# BMS_IC.net
KiCad netlist of a schematic drawn in Altium Designer
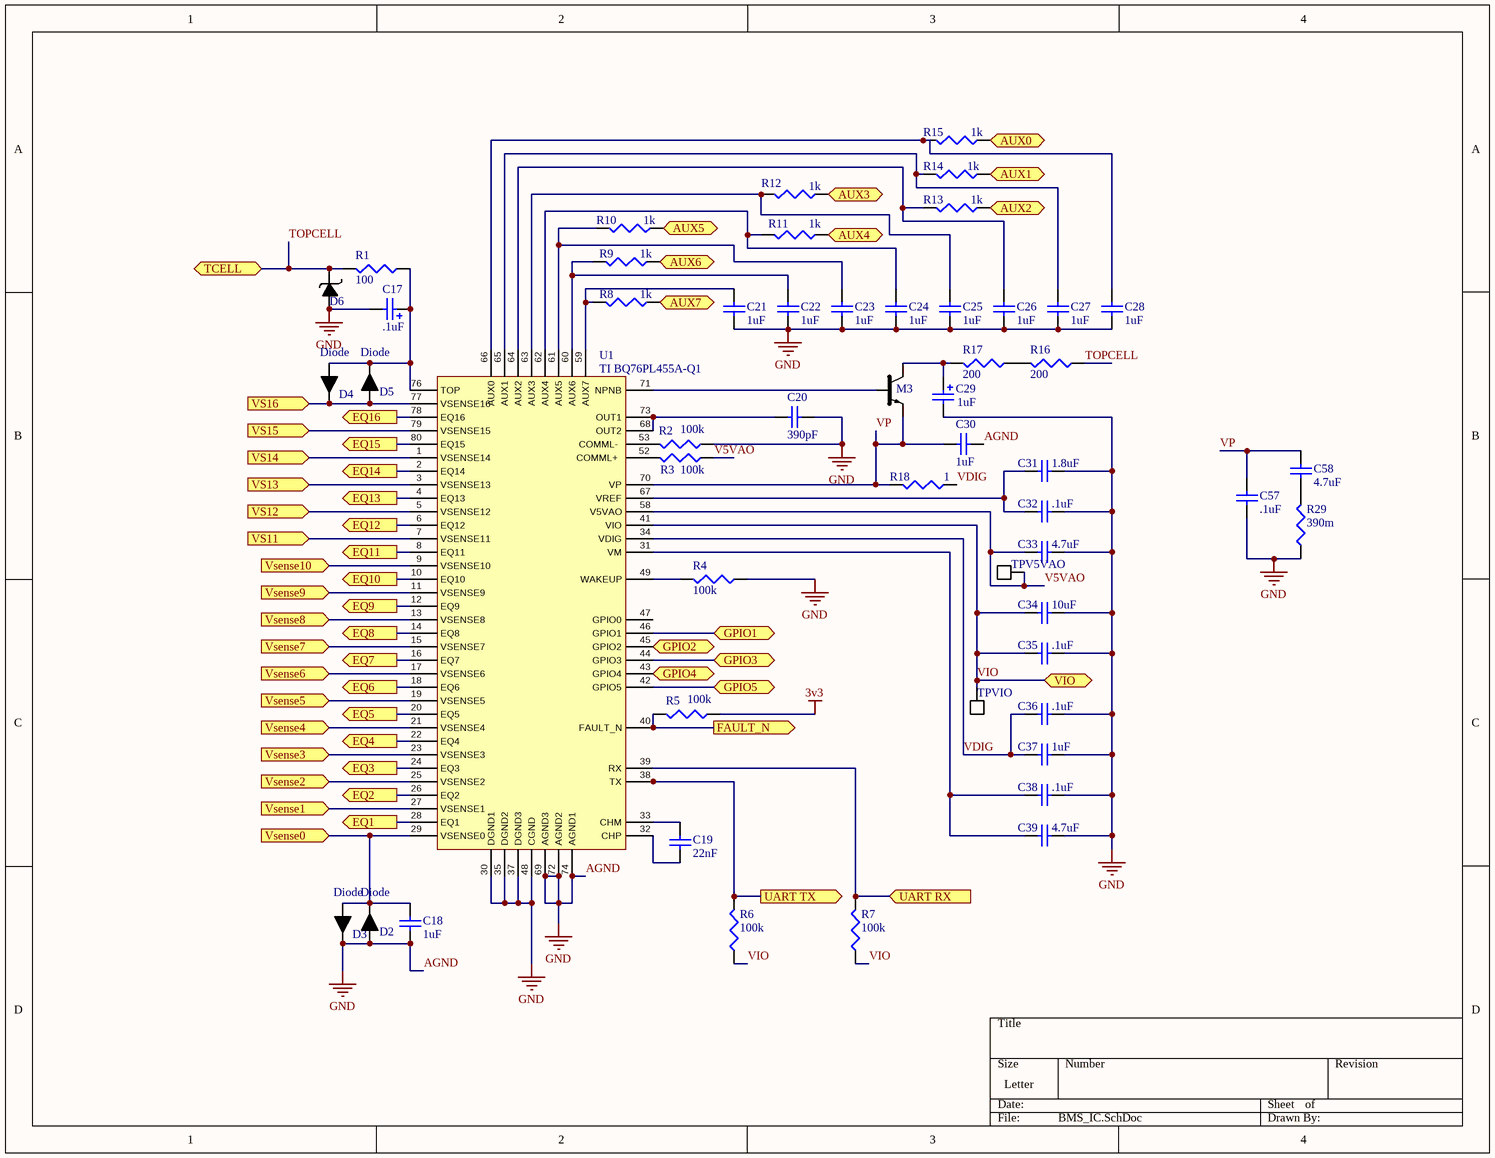
[diagram p0: BMS_IC.SchDoc]

(export (version "E")
  (design (tool "Eeschema 10.0.6"))
  (components
    (comp (ref "C17")
      (value ".1uF")
      (footprint "SMD1206 Polarized")
      (description "Polarized Capacitor (Surface Mount)")
      (fields (field (name "Comment") "Cap"))
      (libsource (lib "Components") (part "Capacitor Polarized"))
    )
    (comp (ref "C18")
      (value "1uF")
      (footprint "SMD0603")
      (description "Ceramic Chip Capacitor")
      (fields (field (name "Comment") "Cap"))
      (libsource (lib "Components") (part "Capacitor Ceramic"))
    )
    (comp (ref "C19")
      (value "22nF")
      (footprint "SMD0603")
      (description "Ceramic Chip Capacitor")
      (fields (field (name "Comment") "Cap"))
      (libsource (lib "Components") (part "Capacitor Ceramic"))
    )
    (comp (ref "C20")
      (value "390pF")
      (footprint "SMD0805")
      (description "Ceramic Chip Capacitor")
      (fields (field (name "Comment") "Cap"))
      (libsource (lib "Components") (part "Capacitor Ceramic"))
    )
    (comp (ref "C21")
      (value "1uF")
      (footprint "SMD0603")
      (description "Ceramic Chip Capacitor")
      (fields (field (name "Comment") "Cap"))
      (libsource (lib "Components") (part "Capacitor Ceramic"))
    )
    (comp (ref "C22")
      (value "1uF")
      (footprint "SMD0603")
      (description "Ceramic Chip Capacitor")
      (fields (field (name "Comment") "Cap"))
      (libsource (lib "Components") (part "Capacitor Ceramic"))
    )
    (comp (ref "C23")
      (value "1uF")
      (footprint "SMD0603")
      (description "Ceramic Chip Capacitor")
      (fields (field (name "Comment") "Cap"))
      (libsource (lib "Components") (part "Capacitor Ceramic"))
    )
    (comp (ref "C24")
      (value "1uF")
      (footprint "SMD0603")
      (description "Ceramic Chip Capacitor")
      (fields (field (name "Comment") "Cap"))
      (libsource (lib "Components") (part "Capacitor Ceramic"))
    )
    (comp (ref "C25")
      (value "1uF")
      (footprint "SMD0603")
      (description "Ceramic Chip Capacitor")
      (fields (field (name "Comment") "Cap"))
      (libsource (lib "Components") (part "Capacitor Ceramic"))
    )
    (comp (ref "C26")
      (value "1uF")
      (footprint "SMD0603")
      (description "Ceramic Chip Capacitor")
      (fields (field (name "Comment") "Cap"))
      (libsource (lib "Components") (part "Capacitor Ceramic"))
    )
    (comp (ref "C27")
      (value "1uF")
      (footprint "SMD0603")
      (description "Ceramic Chip Capacitor")
      (fields (field (name "Comment") "Cap"))
      (libsource (lib "Components") (part "Capacitor Ceramic"))
    )
    (comp (ref "C28")
      (value "1uF")
      (footprint "SMD0603")
      (description "Ceramic Chip Capacitor")
      (fields (field (name "Comment") "Cap"))
      (libsource (lib "Components") (part "Capacitor Ceramic"))
    )
    (comp (ref "C29")
      (value "1uF")
      (footprint "SMD1206 Polarized")
      (description "Polarized Capacitor (Surface Mount)")
      (fields (field (name "Comment") "Cap"))
      (libsource (lib "Components") (part "Capacitor Polarized"))
    )
    (comp (ref "C30")
      (value "1uF")
      (footprint "SMD0603")
      (description "Ceramic Chip Capacitor")
      (fields (field (name "Comment") "Cap"))
      (libsource (lib "Components") (part "Capacitor Ceramic"))
    )
    (comp (ref "C31")
      (value "1.8uF")
      (footprint "SMD0603")
      (description "Ceramic Chip Capacitor")
      (fields (field (name "Comment") "Cap"))
      (libsource (lib "Components") (part "Capacitor Ceramic"))
    )
    (comp (ref "C32")
      (value ".1uF")
      (footprint "SMD0603")
      (description "Ceramic Chip Capacitor")
      (fields (field (name "Comment") "Cap"))
      (libsource (lib "Components") (part "Capacitor Ceramic"))
    )
    (comp (ref "C33")
      (value "4.7uF")
      (footprint "SMD0603")
      (description "Ceramic Chip Capacitor")
      (fields (field (name "Comment") "Cap"))
      (libsource (lib "Components") (part "Capacitor Ceramic"))
    )
    (comp (ref "C34")
      (value "10uF")
      (footprint "SMD0603")
      (description "Ceramic Chip Capacitor")
      (fields (field (name "Comment") "Cap"))
      (libsource (lib "Components") (part "Capacitor Ceramic"))
    )
    (comp (ref "C35")
      (value ".1uF")
      (footprint "SMD0603")
      (description "Ceramic Chip Capacitor")
      (fields (field (name "Comment") "Cap"))
      (libsource (lib "Components") (part "Capacitor Ceramic"))
    )
    (comp (ref "C36")
      (value ".1uF")
      (footprint "SMD0603")
      (description "Ceramic Chip Capacitor")
      (fields (field (name "Comment") "Cap"))
      (libsource (lib "Components") (part "Capacitor Ceramic"))
    )
    (comp (ref "C37")
      (value "1uF")
      (footprint "SMD0603")
      (description "Ceramic Chip Capacitor")
      (fields (field (name "Comment") "Cap"))
      (libsource (lib "Components") (part "Capacitor Ceramic"))
    )
    (comp (ref "C38")
      (value ".1uF")
      (footprint "SMD0603")
      (description "Ceramic Chip Capacitor")
      (fields (field (name "Comment") "Cap"))
      (libsource (lib "Components") (part "Capacitor Ceramic"))
    )
    (comp (ref "C39")
      (value "4.7uF")
      (footprint "SMD0603")
      (description "Ceramic Chip Capacitor")
      (fields (field (name "Comment") "Cap"))
      (libsource (lib "Components") (part "Capacitor Ceramic"))
    )
    (comp (ref "C57")
      (value ".1uF")
      (footprint "SMD0603")
      (description "Ceramic Chip Capacitor")
      (fields (field (name "Comment") "Cap"))
      (libsource (lib "Components") (part "Capacitor Ceramic"))
    )
    (comp (ref "C58")
      (value "4.7uF")
      (footprint "SMD0603")
      (description "Ceramic Chip Capacitor")
      (fields (field (name "Comment") "Cap"))
      (libsource (lib "Components") (part "Capacitor Ceramic"))
    )
    (comp (ref "D2") (value "Diode") (footprint "DPAK23") (libsource (lib "Components") (part "Diode")))
    (comp (ref "D3") (value "Diode") (footprint "DPAK23") (libsource (lib "Components") (part "Diode")))
    (comp (ref "D4") (value "Diode") (footprint "DPAK23") (libsource (lib "Components") (part "Diode")))
    (comp (ref "D5") (value "Diode") (footprint "DPAK23") (libsource (lib "Components") (part "Diode")))
    (comp (ref "D6")
      (value "Zener Diode")
      (footprint "DPAK M:TVS Diode")
      (libsource (lib "Components") (part "Zener Diode"))
    )
    (comp (ref "M3") (value "BJT") (footprint "SOT23") (libsource (lib "Schlib1") (part "BJT")))
    (comp (ref "R1")
      (value "100")
      (footprint "SMD0603")
      (description "Resistor")
      (fields (field (name "Comment") "Res"))
      (libsource (lib "Components") (part "Resistor"))
    )
    (comp (ref "R2")
      (value "100k")
      (footprint "SMD0603")
      (description "Resistor")
      (fields (field (name "Comment") "Res"))
      (libsource (lib "Components") (part "Resistor"))
    )
    (comp (ref "R3")
      (value "100k")
      (footprint "SMD0603")
      (description "Resistor")
      (fields (field (name "Comment") "Res"))
      (libsource (lib "Components") (part "Resistor"))
    )
    (comp (ref "R4")
      (value "100k")
      (footprint "SMD0603")
      (description "Resistor")
      (fields (field (name "Comment") "Res"))
      (libsource (lib "Components") (part "Resistor"))
    )
    (comp (ref "R5")
      (value "100k")
      (footprint "SMD0603")
      (description "Resistor")
      (fields (field (name "Comment") "Res"))
      (libsource (lib "Components") (part "Resistor"))
    )
    (comp (ref "R6")
      (value "100k")
      (footprint "SMD0603")
      (description "Resistor")
      (fields (field (name "Comment") "Res"))
      (libsource (lib "Components") (part "Resistor"))
    )
    (comp (ref "R7")
      (value "100k")
      (footprint "SMD0603")
      (description "Resistor")
      (fields (field (name "Comment") "Res"))
      (libsource (lib "Components") (part "Resistor"))
    )
    (comp (ref "R8")
      (value "1k")
      (footprint "SMD0603")
      (description "Resistor")
      (fields (field (name "Comment") "Res"))
      (libsource (lib "Components") (part "Resistor"))
    )
    (comp (ref "R9")
      (value "1k")
      (footprint "SMD0603")
      (description "Resistor")
      (fields (field (name "Comment") "Res"))
      (libsource (lib "Components") (part "Resistor"))
    )
    (comp (ref "R10")
      (value "1k")
      (footprint "SMD0603")
      (description "Resistor")
      (fields (field (name "Comment") "Res"))
      (libsource (lib "Components") (part "Resistor"))
    )
    (comp (ref "R11")
      (value "1k")
      (footprint "SMD0603")
      (description "Resistor")
      (fields (field (name "Comment") "Res"))
      (libsource (lib "Components") (part "Resistor"))
    )
    (comp (ref "R12")
      (value "1k")
      (footprint "SMD0603")
      (description "Resistor")
      (fields (field (name "Comment") "Res"))
      (libsource (lib "Components") (part "Resistor"))
    )
    (comp (ref "R13")
      (value "1k")
      (footprint "SMD0603")
      (description "Resistor")
      (fields (field (name "Comment") "Res"))
      (libsource (lib "Components") (part "Resistor"))
    )
    (comp (ref "R14")
      (value "1k")
      (footprint "SMD0603")
      (description "Resistor")
      (fields (field (name "Comment") "Res"))
      (libsource (lib "Components") (part "Resistor"))
    )
    (comp (ref "R15")
      (value "1k")
      (footprint "SMD0603")
      (description "Resistor")
      (fields (field (name "Comment") "Res"))
      (libsource (lib "Components") (part "Resistor"))
    )
    (comp (ref "R16")
      (value "200")
      (footprint "SMD0603")
      (description "Resistor")
      (fields (field (name "Comment") "Res"))
      (libsource (lib "Components") (part "Resistor"))
    )
    (comp (ref "R17")
      (value "200")
      (footprint "SMD0603")
      (description "Resistor")
      (fields (field (name "Comment") "Res"))
      (libsource (lib "Components") (part "Resistor"))
    )
    (comp (ref "R18")
      (value "1")
      (footprint "SMD0603")
      (description "Resistor")
      (fields (field (name "Comment") "Res"))
      (libsource (lib "Components") (part "Resistor"))
    )
    (comp (ref "R29")
      (value "390m")
      (footprint "SMD0603")
      (description "Resistor")
      (fields (field (name "Comment") "Res"))
      (libsource (lib "Components") (part "Resistor"))
    )
    (comp (ref "TPV5VAO")
      (value "Test Point")
      (footprint "Test Point")
      (libsource (lib "Components") (part "Test Point"))
    )
    (comp (ref "TPVIO")
      (value "Test Point")
      (footprint "Test Point")
      (libsource (lib "Components") (part "Test Point"))
    )
    (comp (ref "U1")
      (value "TI BQ76PL455A-Q1")
      (footprint "TQFP-80")
      (libsource (lib "SEM_BMS") (part "TI BQ76PL455A-Q1"))
    )
  )
  (nets
    (net (code "1") (name "/AUX0") (class "Default")
      (node (ref "R15") (pin "1") (pinfunction "1_1") (pintype "passive"))
    )
    (net (code "2") (name "/AUX1") (class "Default")
      (node (ref "R14") (pin "1") (pinfunction "1_1") (pintype "passive"))
    )
    (net (code "3") (name "/AUX2") (class "Default")
      (node (ref "R13") (pin "1") (pinfunction "1_1") (pintype "passive"))
    )
    (net (code "4") (name "/AUX3") (class "Default")
      (node (ref "R12") (pin "1") (pinfunction "1_1") (pintype "passive"))
    )
    (net (code "5") (name "/AUX4") (class "Default")
      (node (ref "R11") (pin "1") (pinfunction "1_1") (pintype "passive"))
    )
    (net (code "6") (name "/AUX5") (class "Default")
      (node (ref "R10") (pin "1") (pinfunction "1_1") (pintype "passive"))
    )
    (net (code "7") (name "/AUX6") (class "Default")
      (node (ref "R9") (pin "1") (pinfunction "1_1") (pintype "passive"))
    )
    (net (code "8") (name "/AUX7") (class "Default")
      (node (ref "R8") (pin "1") (pinfunction "1_1") (pintype "passive"))
    )
    (net (code "9") (name "/EQ1") (class "Default")
      (node (ref "U1") (pin "28") (pinfunction "EQ1_28") (pintype "passive"))
    )
    (net (code "10") (name "/EQ2") (class "Default")
      (node (ref "U1") (pin "26") (pinfunction "EQ2_26") (pintype "passive"))
    )
    (net (code "11") (name "/EQ3") (class "Default")
      (node (ref "U1") (pin "24") (pinfunction "EQ3_24") (pintype "passive"))
    )
    (net (code "12") (name "/EQ4") (class "Default")
      (node (ref "U1") (pin "22") (pinfunction "EQ4_22") (pintype "passive"))
    )
    (net (code "13") (name "/EQ5") (class "Default")
      (node (ref "U1") (pin "20") (pinfunction "EQ5_20") (pintype "passive"))
    )
    (net (code "14") (name "/EQ6") (class "Default")
      (node (ref "U1") (pin "18") (pinfunction "EQ6_18") (pintype "passive"))
    )
    (net (code "15") (name "/EQ7") (class "Default")
      (node (ref "U1") (pin "16") (pinfunction "EQ7_16") (pintype "passive"))
    )
    (net (code "16") (name "/EQ8") (class "Default")
      (node (ref "U1") (pin "14") (pinfunction "EQ8_14") (pintype "passive"))
    )
    (net (code "17") (name "/EQ9") (class "Default")
      (node (ref "U1") (pin "12") (pinfunction "EQ9_12") (pintype "passive"))
    )
    (net (code "18") (name "/EQ10") (class "Default")
      (node (ref "U1") (pin "10") (pinfunction "EQ10_10") (pintype "passive"))
    )
    (net (code "19") (name "/EQ11") (class "Default")
      (node (ref "U1") (pin "8") (pinfunction "EQ11_8") (pintype "passive"))
    )
    (net (code "20") (name "/EQ12") (class "Default")
      (node (ref "U1") (pin "6") (pinfunction "EQ12_6") (pintype "passive"))
    )
    (net (code "21") (name "/EQ13") (class "Default")
      (node (ref "U1") (pin "4") (pinfunction "EQ13_4") (pintype "passive"))
    )
    (net (code "22") (name "/EQ14") (class "Default")
      (node (ref "U1") (pin "2") (pinfunction "EQ14_2") (pintype "passive"))
    )
    (net (code "23") (name "/EQ15") (class "Default")
      (node (ref "U1") (pin "80") (pinfunction "EQ15_80") (pintype "passive"))
    )
    (net (code "24") (name "/EQ16") (class "Default")
      (node (ref "U1") (pin "78") (pinfunction "EQ16_78") (pintype "passive"))
    )
    (net (code "25") (name "/FAULT_N") (class "Default")
      (node (ref "R5") (pin "2") (pinfunction "2_2") (pintype "passive"))
      (node (ref "U1") (pin "40") (pinfunction "FAULT_N_40") (pintype "passive"))
    )
    (net (code "26") (name "/GPIO1") (class "Default")
      (node (ref "U1") (pin "46") (pinfunction "GPIO1_46") (pintype "passive"))
    )
    (net (code "27") (name "/GPIO2") (class "Default")
      (node (ref "U1") (pin "45") (pinfunction "GPIO2_45") (pintype "passive"))
    )
    (net (code "28") (name "/GPIO3") (class "Default")
      (node (ref "U1") (pin "44") (pinfunction "GPIO3_44") (pintype "passive"))
    )
    (net (code "29") (name "/GPIO4") (class "Default")
      (node (ref "U1") (pin "43") (pinfunction "GPIO4_43") (pintype "passive"))
    )
    (net (code "30") (name "/GPIO5") (class "Default")
      (node (ref "U1") (pin "42") (pinfunction "GPIO5_42") (pintype "passive"))
    )
    (net (code "31") (name "/TOPCELL") (class "Default")
      (node (ref "D6") (pin "2") (pinfunction "2_2") (pintype "passive"))
      (node (ref "R1") (pin "2") (pinfunction "2_2") (pintype "passive"))
      (node (ref "R16") (pin "1") (pinfunction "1_1") (pintype "passive"))
    )
    (net (code "32") (name "/UART RX") (class "Default")
      (node (ref "R7") (pin "2") (pinfunction "2_2") (pintype "passive"))
      (node (ref "U1") (pin "39") (pinfunction "RX_39") (pintype "passive"))
    )
    (net (code "33") (name "/UART TX") (class "Default")
      (node (ref "R6") (pin "2") (pinfunction "2_2") (pintype "passive"))
      (node (ref "U1") (pin "38") (pinfunction "TX_38") (pintype "passive"))
    )
    (net (code "34") (name "/V5VAO") (class "Default")
      (node (ref "C33") (pin "2") (pinfunction "2_2") (pintype "passive"))
      (node (ref "R3") (pin "1") (pinfunction "1_1") (pintype "passive"))
      (node (ref "TPV5VAO") (pin "1") (pinfunction "1_1") (pintype "passive"))
      (node (ref "U1") (pin "58") (pinfunction "V5VAO_58") (pintype "passive"))
    )
    (net (code "35") (name "/VDIG") (class "Default")
      (node (ref "C36") (pin "2") (pinfunction "2_2") (pintype "passive"))
      (node (ref "C37") (pin "2") (pinfunction "2_2") (pintype "passive"))
      (node (ref "R18") (pin "1") (pinfunction "1_1") (pintype "passive"))
      (node (ref "U1") (pin "34") (pinfunction "VDIG_34") (pintype "passive"))
    )
    (net (code "36") (name "/VIO") (class "Default")
      (node (ref "C34") (pin "2") (pinfunction "2_2") (pintype "passive"))
      (node (ref "C35") (pin "2") (pinfunction "2_2") (pintype "passive"))
      (node (ref "R6") (pin "1") (pinfunction "1_1") (pintype "passive"))
      (node (ref "R7") (pin "1") (pinfunction "1_1") (pintype "passive"))
      (node (ref "TPVIO") (pin "1") (pinfunction "1_1") (pintype "passive"))
      (node (ref "U1") (pin "41") (pinfunction "VIO_41") (pintype "passive"))
    )
    (net (code "37") (name "/VP") (class "Default")
      (node (ref "C30") (pin "2") (pinfunction "2_2") (pintype "passive"))
      (node (ref "C57") (pin "2") (pinfunction "2_2") (pintype "passive"))
      (node (ref "C58") (pin "2") (pinfunction "2_2") (pintype "passive"))
      (node (ref "M3") (pin "3") (pintype "passive"))
      (node (ref "R18") (pin "2") (pinfunction "2_2") (pintype "passive"))
      (node (ref "U1") (pin "70") (pinfunction "VP_70") (pintype "passive"))
    )
    (net (code "38") (name "/VS11") (class "Default")
      (node (ref "U1") (pin "7") (pinfunction "VSENSE11_7") (pintype "passive"))
    )
    (net (code "39") (name "/VS12") (class "Default")
      (node (ref "U1") (pin "5") (pinfunction "VSENSE12_5") (pintype "passive"))
    )
    (net (code "40") (name "/VS13") (class "Default")
      (node (ref "U1") (pin "3") (pinfunction "VSENSE13_3") (pintype "passive"))
    )
    (net (code "41") (name "/VS14") (class "Default")
      (node (ref "U1") (pin "1") (pinfunction "VSENSE14_1") (pintype "passive"))
    )
    (net (code "42") (name "/VS15") (class "Default")
      (node (ref "U1") (pin "79") (pinfunction "VSENSE15_79") (pintype "passive"))
    )
    (net (code "43") (name "/VS16") (class "Default")
      (node (ref "D4") (pin "2") (pinfunction "Cathode_(-)_2") (pintype "passive"))
      (node (ref "D5") (pin "3") (pinfunction "Anode_(+)_3") (pintype "passive"))
      (node (ref "U1") (pin "77") (pinfunction "VSENSE16_77") (pintype "passive"))
    )
    (net (code "44") (name "/Vsense0") (class "Default")
      (node (ref "C18") (pin "2") (pinfunction "2_2") (pintype "passive"))
      (node (ref "D2") (pin "2") (pinfunction "Cathode_(-)_2") (pintype "passive"))
      (node (ref "D3") (pin "3") (pinfunction "Anode_(+)_3") (pintype "passive"))
      (node (ref "U1") (pin "29") (pinfunction "VSENSE0_29") (pintype "passive"))
    )
    (net (code "45") (name "/Vsense1") (class "Default")
      (node (ref "U1") (pin "27") (pinfunction "VSENSE1_27") (pintype "passive"))
    )
    (net (code "46") (name "/Vsense2") (class "Default")
      (node (ref "U1") (pin "25") (pinfunction "VSENSE2_25") (pintype "passive"))
    )
    (net (code "47") (name "/Vsense3") (class "Default")
      (node (ref "U1") (pin "23") (pinfunction "VSENSE3_23") (pintype "passive"))
    )
    (net (code "48") (name "/Vsense4") (class "Default")
      (node (ref "U1") (pin "21") (pinfunction "VSENSE4_21") (pintype "passive"))
    )
    (net (code "49") (name "/Vsense5") (class "Default")
      (node (ref "U1") (pin "19") (pinfunction "VSENSE5_19") (pintype "passive"))
    )
    (net (code "50") (name "/Vsense6") (class "Default")
      (node (ref "U1") (pin "17") (pinfunction "VSENSE6_17") (pintype "passive"))
    )
    (net (code "51") (name "/Vsense7") (class "Default")
      (node (ref "U1") (pin "15") (pinfunction "VSENSE7_15") (pintype "passive"))
    )
    (net (code "52") (name "/Vsense8") (class "Default")
      (node (ref "U1") (pin "13") (pinfunction "VSENSE8_13") (pintype "passive"))
    )
    (net (code "53") (name "/Vsense9") (class "Default")
      (node (ref "U1") (pin "11") (pinfunction "VSENSE9_11") (pintype "passive"))
    )
    (net (code "54") (name "/Vsense10") (class "Default")
      (node (ref "U1") (pin "9") (pinfunction "VSENSE10_9") (pintype "passive"))
    )
    (net (code "55") (name "3v3") (class "Default")
      (node (ref "R5") (pin "1") (pinfunction "1_1") (pintype "passive"))
    )
    (net (code "56") (name "GND") (class "Default")
      (node (ref "C17") (pin "2") (pinfunction "2_2") (pintype "passive"))
      (node (ref "C18") (pin "1") (pinfunction "1_1") (pintype "passive"))
      (node (ref "C20") (pin "1") (pinfunction "1_1") (pintype "passive"))
      (node (ref "C21") (pin "1") (pinfunction "1_1") (pintype "passive"))
      (node (ref "C22") (pin "1") (pinfunction "1_1") (pintype "passive"))
      (node (ref "C23") (pin "1") (pinfunction "1_1") (pintype "passive"))
      (node (ref "C24") (pin "1") (pinfunction "1_1") (pintype "passive"))
      (node (ref "C25") (pin "1") (pinfunction "1_1") (pintype "passive"))
      (node (ref "C26") (pin "1") (pinfunction "1_1") (pintype "passive"))
      (node (ref "C27") (pin "1") (pinfunction "1_1") (pintype "passive"))
      (node (ref "C28") (pin "1") (pinfunction "1_1") (pintype "passive"))
      (node (ref "C29") (pin "2") (pinfunction "2_2") (pintype "passive"))
      (node (ref "C30") (pin "1") (pinfunction "1_1") (pintype "passive"))
      (node (ref "C31") (pin "1") (pinfunction "1_1") (pintype "passive"))
      (node (ref "C32") (pin "1") (pinfunction "1_1") (pintype "passive"))
      (node (ref "C33") (pin "1") (pinfunction "1_1") (pintype "passive"))
      (node (ref "C34") (pin "1") (pinfunction "1_1") (pintype "passive"))
      (node (ref "C35") (pin "1") (pinfunction "1_1") (pintype "passive"))
      (node (ref "C36") (pin "1") (pinfunction "1_1") (pintype "passive"))
      (node (ref "C37") (pin "1") (pinfunction "1_1") (pintype "passive"))
      (node (ref "C38") (pin "1") (pinfunction "1_1") (pintype "passive"))
      (node (ref "C39") (pin "1") (pinfunction "1_1") (pintype "passive"))
      (node (ref "C57") (pin "1") (pinfunction "1_1") (pintype "passive"))
      (node (ref "D2") (pin "3") (pinfunction "Anode_(+)_3") (pintype "passive"))
      (node (ref "D3") (pin "2") (pinfunction "Cathode_(-)_2") (pintype "passive"))
      (node (ref "D6") (pin "1") (pintype "passive"))
      (node (ref "R2") (pin "1") (pinfunction "1_1") (pintype "passive"))
      (node (ref "R29") (pin "1") (pinfunction "1_1") (pintype "passive"))
      (node (ref "R4") (pin "1") (pinfunction "1_1") (pintype "passive"))
      (node (ref "U1") (pin "30") (pinfunction "DGND1_30") (pintype "passive"))
      (node (ref "U1") (pin "35") (pinfunction "DGND2_35") (pintype "passive"))
      (node (ref "U1") (pin "37") (pinfunction "DGND3_37") (pintype "passive"))
      (node (ref "U1") (pin "48") (pinfunction "CGND_48") (pintype "passive"))
      (node (ref "U1") (pin "69") (pinfunction "AGND3_69") (pintype "passive"))
      (node (ref "U1") (pin "72") (pinfunction "AGND2_72") (pintype "passive"))
      (node (ref "U1") (pin "74") (pinfunction "AGND1_74") (pintype "passive"))
    )
    (net (code "57") (name "Net-(C29-Pad1)") (class "Default")
      (node (ref "C29") (pin "1") (pinfunction "1_1") (pintype "passive"))
      (node (ref "M3") (pin "1") (pintype "passive"))
      (node (ref "R17") (pin "2") (pinfunction "2_2") (pintype "passive"))
    )
    (net (code "58") (name "Net-(C58-Pad1)") (class "Default")
      (node (ref "C58") (pin "1") (pinfunction "1_1") (pintype "passive"))
      (node (ref "R29") (pin "2") (pinfunction "2_2") (pintype "passive"))
    )
    (net (code "59") (name "Net-(D4-Anode_(+))") (class "Default")
      (node (ref "C17") (pin "1") (pinfunction "1_1") (pintype "passive"))
      (node (ref "D4") (pin "3") (pinfunction "Anode_(+)_3") (pintype "passive"))
      (node (ref "D5") (pin "2") (pinfunction "Cathode_(-)_2") (pintype "passive"))
      (node (ref "R1") (pin "1") (pinfunction "1_1") (pintype "passive"))
      (node (ref "U1") (pin "76") (pinfunction "TOP_76") (pintype "passive"))
    )
    (net (code "60") (name "Net-(R16-Pad2)") (class "Default")
      (node (ref "R16") (pin "2") (pinfunction "2_2") (pintype "passive"))
      (node (ref "R17") (pin "1") (pinfunction "1_1") (pintype "passive"))
    )
    (net (code "61") (name "Net-(U1-AUX0)") (class "Default")
      (node (ref "C28") (pin "2") (pinfunction "2_2") (pintype "passive"))
      (node (ref "R15") (pin "2") (pinfunction "2_2") (pintype "passive"))
      (node (ref "U1") (pin "66") (pinfunction "AUX0_66") (pintype "passive"))
    )
    (net (code "62") (name "Net-(U1-AUX1)") (class "Default")
      (node (ref "C27") (pin "2") (pinfunction "2_2") (pintype "passive"))
      (node (ref "R14") (pin "2") (pinfunction "2_2") (pintype "passive"))
      (node (ref "U1") (pin "65") (pinfunction "AUX1_65") (pintype "passive"))
    )
    (net (code "63") (name "Net-(U1-AUX2)") (class "Default")
      (node (ref "C26") (pin "2") (pinfunction "2_2") (pintype "passive"))
      (node (ref "R13") (pin "2") (pinfunction "2_2") (pintype "passive"))
      (node (ref "U1") (pin "64") (pinfunction "AUX2_64") (pintype "passive"))
    )
    (net (code "64") (name "Net-(U1-AUX3)") (class "Default")
      (node (ref "C25") (pin "2") (pinfunction "2_2") (pintype "passive"))
      (node (ref "R12") (pin "2") (pinfunction "2_2") (pintype "passive"))
      (node (ref "U1") (pin "63") (pinfunction "AUX3_63") (pintype "passive"))
    )
    (net (code "65") (name "Net-(U1-AUX4)") (class "Default")
      (node (ref "C24") (pin "2") (pinfunction "2_2") (pintype "passive"))
      (node (ref "R11") (pin "2") (pinfunction "2_2") (pintype "passive"))
      (node (ref "U1") (pin "62") (pinfunction "AUX4_62") (pintype "passive"))
    )
    (net (code "66") (name "Net-(U1-AUX5)") (class "Default")
      (node (ref "C23") (pin "2") (pinfunction "2_2") (pintype "passive"))
      (node (ref "R10") (pin "2") (pinfunction "2_2") (pintype "passive"))
      (node (ref "U1") (pin "61") (pinfunction "AUX5_61") (pintype "passive"))
    )
    (net (code "67") (name "Net-(U1-AUX6)") (class "Default")
      (node (ref "C22") (pin "2") (pinfunction "2_2") (pintype "passive"))
      (node (ref "R9") (pin "2") (pinfunction "2_2") (pintype "passive"))
      (node (ref "U1") (pin "60") (pinfunction "AUX6_60") (pintype "passive"))
    )
    (net (code "68") (name "Net-(U1-AUX7)") (class "Default")
      (node (ref "C21") (pin "2") (pinfunction "2_2") (pintype "passive"))
      (node (ref "R8") (pin "2") (pinfunction "2_2") (pintype "passive"))
      (node (ref "U1") (pin "59") (pinfunction "AUX7_59") (pintype "passive"))
    )
    (net (code "69") (name "Net-(U1-CHM)") (class "Default")
      (node (ref "C19") (pin "2") (pinfunction "2_2") (pintype "passive"))
      (node (ref "U1") (pin "33") (pinfunction "CHM_33") (pintype "passive"))
    )
    (net (code "70") (name "Net-(U1-CHP)") (class "Default")
      (node (ref "C19") (pin "1") (pinfunction "1_1") (pintype "passive"))
      (node (ref "U1") (pin "32") (pinfunction "CHP_32") (pintype "passive"))
    )
    (net (code "71") (name "Net-(U1-COMML+)") (class "Default")
      (node (ref "R3") (pin "2") (pinfunction "2_2") (pintype "passive"))
      (node (ref "U1") (pin "52") (pinfunction "COMML+_52") (pintype "passive"))
    )
    (net (code "72") (name "Net-(U1-COMML-)") (class "Default")
      (node (ref "R2") (pin "2") (pinfunction "2_2") (pintype "passive"))
      (node (ref "U1") (pin "53") (pinfunction "COMML-_53") (pintype "passive"))
    )
    (net (code "73") (name "Net-(U1-NPNB)") (class "Default")
      (node (ref "M3") (pin "2") (pintype "passive"))
      (node (ref "U1") (pin "71") (pinfunction "NPNB_71") (pintype "passive"))
    )
    (net (code "74") (name "Net-(U1-OUT1)") (class "Default")
      (node (ref "C20") (pin "2") (pinfunction "2_2") (pintype "passive"))
      (node (ref "U1") (pin "68") (pinfunction "OUT2_68") (pintype "passive"))
      (node (ref "U1") (pin "73") (pinfunction "OUT1_73") (pintype "passive"))
    )
    (net (code "75") (name "Net-(U1-VM)") (class "Default")
      (node (ref "C38") (pin "2") (pinfunction "2_2") (pintype "passive"))
      (node (ref "C39") (pin "2") (pinfunction "2_2") (pintype "passive"))
      (node (ref "U1") (pin "31") (pinfunction "VM_31") (pintype "passive"))
    )
    (net (code "76") (name "Net-(U1-VREF)") (class "Default")
      (node (ref "C31") (pin "2") (pinfunction "2_2") (pintype "passive"))
      (node (ref "C32") (pin "2") (pinfunction "2_2") (pintype "passive"))
      (node (ref "U1") (pin "67") (pinfunction "VREF_67") (pintype "passive"))
    )
    (net (code "77") (name "Net-(U1-WAKEUP)") (class "Default")
      (node (ref "R4") (pin "2") (pinfunction "2_2") (pintype "passive"))
      (node (ref "U1") (pin "49") (pinfunction "WAKEUP_49") (pintype "passive"))
    )
    (net (code "78") (name "unconnected-(U1-GPIO0-Pad47)") (class "Default")
      (node (ref "U1") (pin "47") (pinfunction "GPIO0_47") (pintype "passive"))
    )
  )
)
